# DCv1_4.net
KiCad netlist of a schematic drawn in Altium Designer
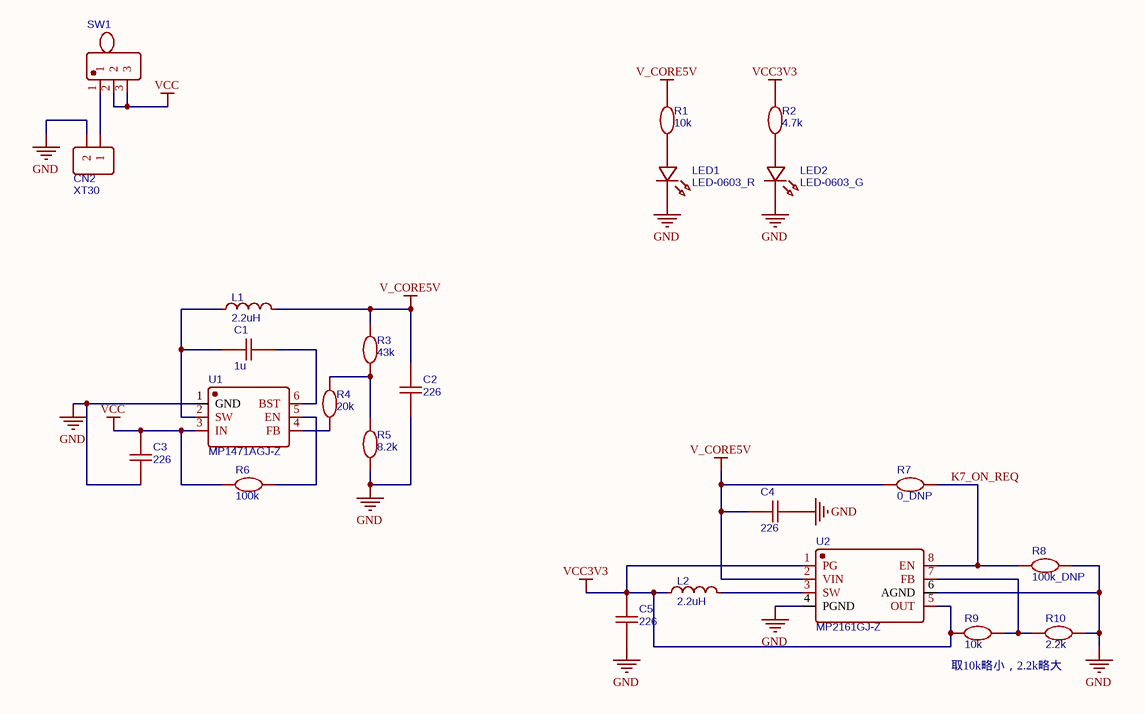
[diagram p0: DCv1.4.SchDoc]

(export (version "E")
  (design (tool "Eeschema 10.0.6"))
  (components
    (comp (ref "C1")
      (value "1u")
      (footprint "C0603")
      (fields (field (name "CONTRIBUTOR") "LCEDA_Lib"))
      (libsource (lib "JLC") (part "C0603"))
    )
    (comp (ref "C2")
      (value "226")
      (footprint "C0603")
      (fields (field (name "CONTRIBUTOR") "LCEDA_Lib"))
      (libsource (lib "JLC") (part "C0603"))
    )
    (comp (ref "C3")
      (value "226")
      (footprint "C0603")
      (fields (field (name "CONTRIBUTOR") "LCEDA_Lib"))
      (libsource (lib "JLC") (part "C0603"))
    )
    (comp (ref "C4")
      (value "226")
      (footprint "C0603")
      (fields (field (name "CONTRIBUTOR") "LCEDA_Lib"))
      (libsource (lib "JLC") (part "C0603"))
    )
    (comp (ref "C5")
      (value "226")
      (footprint "C0603")
      (fields (field (name "CONTRIBUTOR") "LCEDA_Lib"))
      (libsource (lib "JLC") (part "C0603"))
    )
    (comp (ref "CN2")
      (value "XT30")
      (footprint "CONN-TH_XT30UPB-F")
      (fields
        (field (name "BOM_SUPPLIER PART") "C108769")
        (field (name "BOM_MANUFACTURER PART") "XT30UPB-F")
        (field (name "CONTRIBUTOR") "LCSC")
      )
      (libsource (lib "JLC") (part "XT30"))
    )
    (comp (ref "L1")
      (value "2.2uH")
      (footprint "IND-SMD_L4.4-W4.2")
      (fields
        (field (name "BOM_SUPPLIER PART") "C167206")
        (field (name "BOM_MANUFACTURER PART") "FXL0420-2R2-M")
        (field (name "CONTRIBUTOR") "LCSC")
      )
      (libsource (lib "JLC") (part "L0420"))
    )
    (comp (ref "L2")
      (value "2.2uH")
      (footprint "IND-SMD_L4.4-W4.2")
      (fields
        (field (name "BOM_SUPPLIER PART") "C167206")
        (field (name "BOM_MANUFACTURER PART") "FXL0420-2R2-M")
        (field (name "CONTRIBUTOR") "LCSC")
      )
      (libsource (lib "JLC") (part "L0420"))
    )
    (comp (ref "LED1")
      (value "LED-0603_R")
      (footprint "LED0603_RED")
      (fields
        (field (name "BOM_MANUFACTURER PART") "19-217/R6C-AL1M2VY/3T")
        (field (name "BOM_SUPPLIER PART") "C72044")
        (field (name "CONTRIBUTOR") "LCEDA_01")
      )
      (libsource (lib "JLC") (part "LED-0603_R"))
    )
    (comp (ref "LED2")
      (value "LED-0603_G")
      (footprint "LED0603_GREEN")
      (fields
        (field (name "BOM_MANUFACTURER PART") "19-217/GHC-YR1S2/3T")
        (field (name "BOM_SUPPLIER PART") "C72043")
        (field (name "CONTRIBUTOR") "LCEDA_Lib")
      )
      (libsource (lib "JLC") (part "LED-0603_G"))
    )
    (comp (ref "R1")
      (value "10k")
      (footprint "R0603")
      (fields (field (name "CONTRIBUTOR") "LCEDA_Lib"))
      (libsource (lib "JLC") (part "R0603"))
    )
    (comp (ref "R2")
      (value "4.7k")
      (footprint "R0603")
      (fields (field (name "CONTRIBUTOR") "LCEDA_Lib"))
      (libsource (lib "JLC") (part "R0603"))
    )
    (comp (ref "R3")
      (value "43k")
      (footprint "R0603")
      (fields (field (name "CONTRIBUTOR") "LCEDA_Lib"))
      (libsource (lib "JLC") (part "R0603"))
    )
    (comp (ref "R4")
      (value "20k")
      (footprint "R0603")
      (fields (field (name "CONTRIBUTOR") "LCEDA_Lib"))
      (libsource (lib "JLC") (part "R0603"))
    )
    (comp (ref "R5")
      (value "8.2k")
      (footprint "R0603")
      (fields (field (name "CONTRIBUTOR") "LCEDA_Lib"))
      (libsource (lib "JLC") (part "R0603"))
    )
    (comp (ref "R6")
      (value "100k")
      (footprint "R0603")
      (fields (field (name "CONTRIBUTOR") "LCEDA_Lib"))
      (libsource (lib "JLC") (part "R0603"))
    )
    (comp (ref "R7")
      (value "0_DNP")
      (footprint "R0603")
      (fields (field (name "CONTRIBUTOR") "LCEDA_Lib"))
      (libsource (lib "JLC") (part "R0603"))
    )
    (comp (ref "R8")
      (value "100k_DNP")
      (footprint "R0603")
      (fields (field (name "CONTRIBUTOR") "LCEDA_Lib"))
      (libsource (lib "JLC") (part "R0603"))
    )
    (comp (ref "R9")
      (value "10k")
      (footprint "R0603")
      (fields (field (name "CONTRIBUTOR") "LCEDA_Lib"))
      (libsource (lib "JLC") (part "R0603"))
    )
    (comp (ref "R10")
      (value "2.2k")
      (footprint "R0603")
      (fields (field (name "CONTRIBUTOR") "LCEDA_Lib"))
      (libsource (lib "JLC") (part "R0603"))
    )
    (comp (ref "SW1")
      (value "2MS1T1B1M1QES-5")
      (footprint "SW-TH_2MD1T1B1M1QES-5")
      (fields (field (name "BOM_SUPPLIER PART") "C496169") (field (name "CONTRIBUTOR") "LCSC"))
      (libsource (lib "JLC") (part "2MS1T1B1M1QES-5"))
    )
    (comp (ref "U1")
      (value "MP1471AGJ-Z")
      (footprint "TSOT-23-6_L2.9-W1.6-P0.95-LS2.8-BR")
      (fields (field (name "BOM_SUPPLIER PART") "C58565"))
      (libsource (lib "JLC") (part "MP1471AGJ-Z"))
    )
    (comp (ref "U2")
      (value "MP2161GJ-Z")
      (footprint "TSOT-23-8_L2.9-W1.6-P0.65-LS2.8-BR")
      (fields (field (name "BOM_SUPPLIER PART") "C84831"))
      (libsource (lib "JLC") (part "MP2161GJ-Z"))
    )
  )
  (nets
    (net (code "1") (name "/K7_ON_REQ") (class "Default")
      (node (ref "R7") (pin "2") (pinfunction "2_2") (pintype "passive"))
      (node (ref "R8") (pin "1") (pinfunction "1_1") (pintype "passive"))
      (node (ref "U2") (pin "8") (pinfunction "EN_8") (pintype "passive"))
    )
    (net (code "2") (name "GND") (class "Default")
      (node (ref "C2") (pin "1") (pinfunction "1_1") (pintype "passive"))
      (node (ref "C3") (pin "1") (pinfunction "1_1") (pintype "passive"))
      (node (ref "C4") (pin "1") (pinfunction "1_1") (pintype "passive"))
      (node (ref "C5") (pin "1") (pinfunction "1_1") (pintype "passive"))
      (node (ref "CN2") (pin "2") (pinfunction "2_2") (pintype "passive"))
      (node (ref "LED1") (pin "2") (pinfunction "2_2") (pintype "passive"))
      (node (ref "LED2") (pin "2") (pinfunction "2_2") (pintype "passive"))
      (node (ref "R10") (pin "2") (pinfunction "2_2") (pintype "passive"))
      (node (ref "R5") (pin "1") (pinfunction "1_1") (pintype "passive"))
      (node (ref "R8") (pin "2") (pinfunction "2_2") (pintype "passive"))
      (node (ref "U1") (pin "1") (pinfunction "GND_1") (pintype "passive"))
      (node (ref "U2") (pin "4") (pinfunction "PGND_4") (pintype "passive"))
      (node (ref "U2") (pin "6") (pinfunction "AGND_6") (pintype "passive"))
    )
    (net (code "3") (name "Net-(CN2-Pad1)") (class "Default")
      (node (ref "CN2") (pin "1") (pinfunction "1_1") (pintype "passive"))
      (node (ref "SW1") (pin "1") (pinfunction "1_1") (pintype "passive"))
    )
    (net (code "4") (name "Net-(LED1-Pad1)") (class "Default")
      (node (ref "LED1") (pin "1") (pinfunction "1_1") (pintype "passive"))
      (node (ref "R1") (pin "1") (pinfunction "1_1") (pintype "passive"))
    )
    (net (code "5") (name "Net-(LED2-Pad1)") (class "Default")
      (node (ref "LED2") (pin "1") (pinfunction "1_1") (pintype "passive"))
      (node (ref "R2") (pin "1") (pinfunction "1_1") (pintype "passive"))
    )
    (net (code "6") (name "Net-(R3-Pad1)") (class "Default")
      (node (ref "R3") (pin "1") (pinfunction "1_1") (pintype "passive"))
      (node (ref "R4") (pin "2") (pinfunction "2_2") (pintype "passive"))
      (node (ref "R5") (pin "2") (pinfunction "2_2") (pintype "passive"))
    )
    (net (code "7") (name "Net-(U1-BST)") (class "Default")
      (node (ref "C1") (pin "2") (pinfunction "2_2") (pintype "passive"))
      (node (ref "U1") (pin "6") (pinfunction "BST_6") (pintype "passive"))
    )
    (net (code "8") (name "Net-(U1-EN)") (class "Default")
      (node (ref "R6") (pin "1") (pinfunction "1_1") (pintype "passive"))
      (node (ref "U1") (pin "5") (pinfunction "EN_5") (pintype "passive"))
    )
    (net (code "9") (name "Net-(U1-FB)") (class "Default")
      (node (ref "R4") (pin "1") (pinfunction "1_1") (pintype "passive"))
      (node (ref "U1") (pin "4") (pinfunction "FB_4") (pintype "passive"))
    )
    (net (code "10") (name "Net-(U1-SW)") (class "Default")
      (node (ref "C1") (pin "1") (pinfunction "1_1") (pintype "passive"))
      (node (ref "L1") (pin "1") (pinfunction "1_1") (pintype "passive"))
      (node (ref "U1") (pin "2") (pinfunction "SW_2") (pintype "passive"))
    )
    (net (code "11") (name "Net-(U2-FB)") (class "Default")
      (node (ref "R10") (pin "1") (pinfunction "1_1") (pintype "passive"))
      (node (ref "R9") (pin "2") (pinfunction "2_2") (pintype "passive"))
      (node (ref "U2") (pin "7") (pinfunction "FB_7") (pintype "passive"))
    )
    (net (code "12") (name "Net-(U2-SW)") (class "Default")
      (node (ref "L2") (pin "2") (pinfunction "2_2") (pintype "passive"))
      (node (ref "U2") (pin "3") (pinfunction "SW_3") (pintype "passive"))
    )
    (net (code "13") (name "VCC") (class "Default")
      (node (ref "C3") (pin "2") (pinfunction "2_2") (pintype "passive"))
      (node (ref "R6") (pin "2") (pinfunction "2_2") (pintype "passive"))
      (node (ref "SW1") (pin "2") (pinfunction "2_2") (pintype "passive"))
      (node (ref "SW1") (pin "3") (pinfunction "3_3") (pintype "passive"))
      (node (ref "U1") (pin "3") (pinfunction "IN_3") (pintype "passive"))
    )
    (net (code "14") (name "VCC3V3") (class "Default")
      (node (ref "C5") (pin "2") (pinfunction "2_2") (pintype "passive"))
      (node (ref "L2") (pin "1") (pinfunction "1_1") (pintype "passive"))
      (node (ref "R2") (pin "2") (pinfunction "2_2") (pintype "passive"))
      (node (ref "R9") (pin "1") (pinfunction "1_1") (pintype "passive"))
      (node (ref "U2") (pin "1") (pinfunction "PG_1") (pintype "passive"))
      (node (ref "U2") (pin "5") (pinfunction "OUT_5") (pintype "passive"))
    )
    (net (code "15") (name "V_CORE5V") (class "Default")
      (node (ref "C2") (pin "2") (pinfunction "2_2") (pintype "passive"))
      (node (ref "C4") (pin "2") (pinfunction "2_2") (pintype "passive"))
      (node (ref "L1") (pin "2") (pinfunction "2_2") (pintype "passive"))
      (node (ref "R1") (pin "2") (pinfunction "2_2") (pintype "passive"))
      (node (ref "R3") (pin "2") (pinfunction "2_2") (pintype "passive"))
      (node (ref "R7") (pin "1") (pinfunction "1_1") (pintype "passive"))
      (node (ref "U2") (pin "2") (pinfunction "VIN_2") (pintype "passive"))
    )
  )
)
